# Sensor_Package.net
KiCad netlist of a schematic drawn in Altium Designer
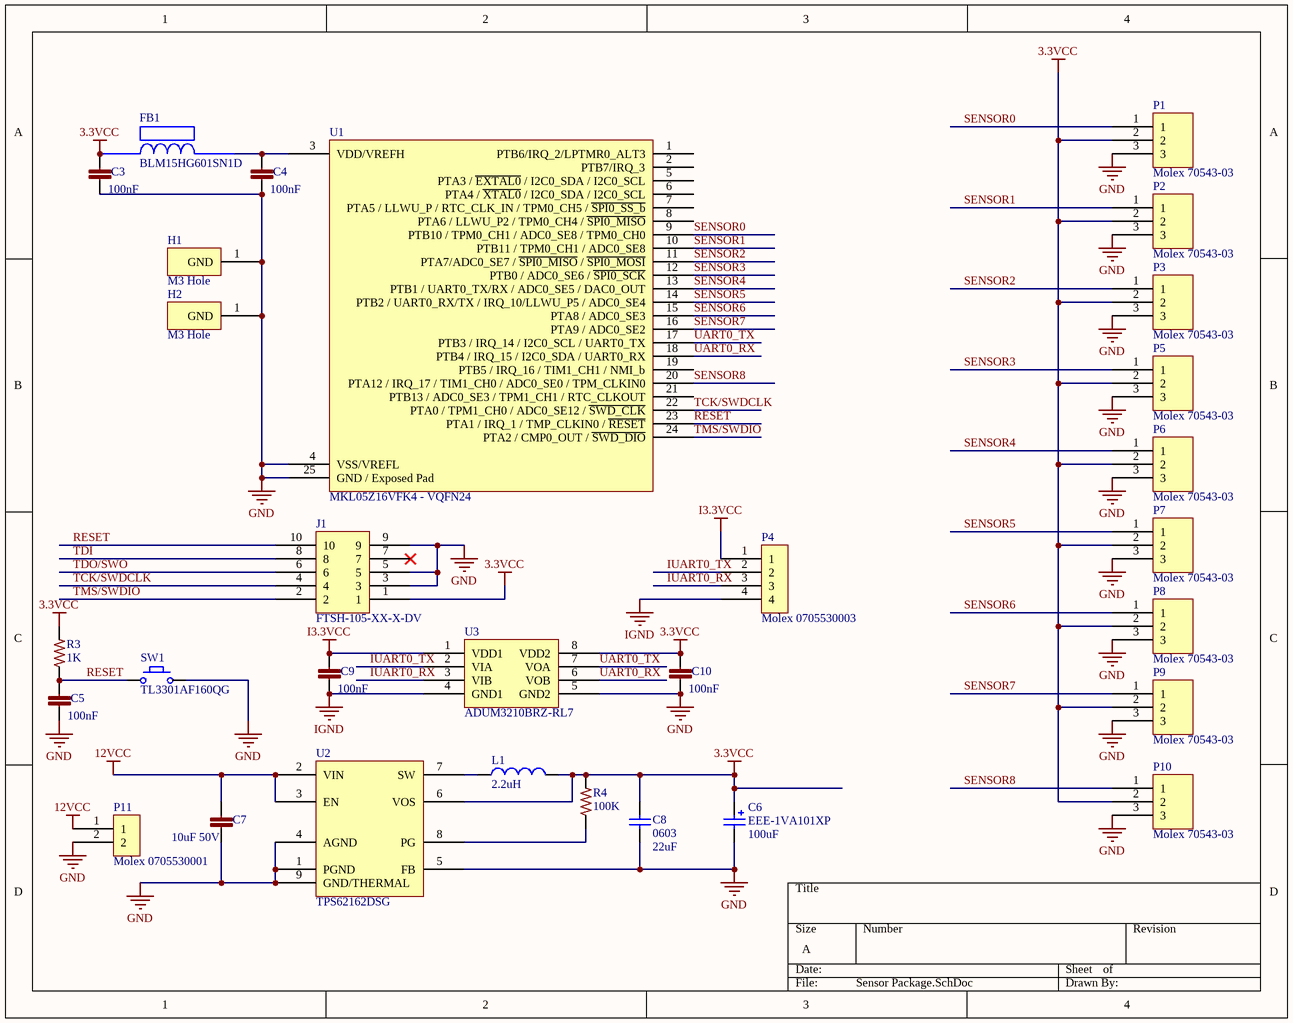
[diagram p0: Sensor Package.SchDoc]

(export (version "E")
  (design (tool "Eeschema 10.0.6"))
  (components
    (comp (ref "C3")
      (value "100nF")
      (footprint "C0402")
      (description "CAP CER 0402 100nF 16V 10% X7R")
      (fields
        (field (name "MANUFACTURERPARTNUMBER") "GRM155R71C104KA88D")
        (field (name "PUBLISHER") "UltiMachine")
      )
      (libsource (lib "3Delight") (part "GRM155R71C104KA88D"))
    )
    (comp (ref "C4")
      (value "100nF")
      (footprint "C0402")
      (description "CAP CER 0402 100nF 16V 10% X7R")
      (fields
        (field (name "MANUFACTURERPARTNUMBER") "GRM155R71C104KA88D")
        (field (name "PUBLISHER") "UltiMachine")
      )
      (libsource (lib "3Delight") (part "GRM155R71C104KA88D"))
    )
    (comp (ref "C5")
      (value "100nF")
      (footprint "C0402")
      (description "CAP CER 0402 100nF 16V 10% X7R")
      (fields
        (field (name "MANUFACTURERPARTNUMBER") "GRM155R71C104KA88D")
        (field (name "PUBLISHER") "UltiMachine")
      )
      (libsource (lib "3Delight") (part "GRM155R71C104KA88D"))
    )
    (comp (ref "C6")
      (value "EEE-1VA101XP")
      (footprint "EEE-1VA101XP")
      (description "CAP ALUM 100UF 35V 20% SMD")
      (fields (field (name "DIGIKEY PART #") "PCE3951CT-ND") (field (name "ALTIUM_VALUE") "100uF"))
      (libsource (lib "Tigershark3D") (part "EEE-1VA101XP"))
    )
    (comp (ref "C7")
      (value "10uF 50V")
      (footprint "C1206")
      (description "CAP CER 10UF 50V 10% X5R 1206")
      (fields
        (field (name "MANUFACTURER") "Samsung")
        (field (name "MANUFACTURERPARTNUMBER") "CL31A106KBHNNNE")
        (field (name "PUBLISHER") "UltiMachine")
      )
      (libsource (lib "Tigershark3D") (part "CL31A106KBHNNNE"))
    )
    (comp (ref "C8")
      (value "0603")
      (footprint "C0805")
      (description "CAP CER 22UF 6.3V 10% X5R 0805")
      (fields
        (field (name "MFR PART #") "CL21A226KQQNNNE")
        (field (name "MFR") "Samsung")
        (field (name "ALTIUM_VALUE") "22uF")
      )
      (libsource (lib "Sensor Package") (part "CL21A226KQQNNNE"))
    )
    (comp (ref "C9")
      (value "100nF")
      (footprint "C0402")
      (description "CAP CER 0402 100nF 16V 10% X7R")
      (fields
        (field (name "MANUFACTURERPARTNUMBER") "GRM155R71C104KA88D")
        (field (name "PUBLISHER") "UltiMachine")
      )
      (libsource (lib "3Delight") (part "GRM155R71C104KA88D"))
    )
    (comp (ref "C10")
      (value "100nF")
      (footprint "C0402")
      (description "CAP CER 0402 100nF 16V 10% X7R")
      (fields
        (field (name "MANUFACTURERPARTNUMBER") "GRM155R71C104KA88D")
        (field (name "PUBLISHER") "UltiMachine")
      )
      (libsource (lib "3Delight") (part "GRM155R71C104KA88D"))
    )
    (comp (ref "FB1")
      (value "BLM15HG601SN1D")
      (footprint "BLM18PG121SN1D")
      (libsource (lib "AHD Part Library") (part "BLM15HG601SN1D"))
    )
    (comp (ref "H1")
      (value "M3 Hole")
      (footprint "Hole-3mm")
      (description "3mm Hole")
      (libsource (lib "Sensor Package") (part "Hole"))
    )
    (comp (ref "H2")
      (value "M3 Hole")
      (footprint "Hole-3mm")
      (description "3mm Hole")
      (libsource (lib "Sensor Package") (part "Hole"))
    )
    (comp (ref "J1")
      (value "FTSH-105-XX-X-DV")
      (footprint "FTSH-105-XX-X-DV")
      (libsource (lib "Adams Altium Library") (part "ARM Cortex JTAG-DEBUG Header"))
    )
    (comp (ref "L1")
      (value "2.2uH")
      (footprint "VLS252012T-2R2M1R3")
      (description "VLS252012T-2R2M1R3")
      (fields (field (name "MFR") "TDK Corporation") (field (name "PUBLISHER") "Adam Vadala-Roth"))
      (libsource (lib "Sensor Package") (part "VLS252012T-2R2M1R3"))
    )
    (comp (ref "P1")
      (value "Molex 70543-03")
      (footprint "70543-03")
      (libsource (lib "RADMBo Schematic Library") (part "Molex Endstop"))
    )
    (comp (ref "P2")
      (value "Molex 70543-03")
      (footprint "70543-03")
      (libsource (lib "RADMBo Schematic Library") (part "Molex Endstop"))
    )
    (comp (ref "P3")
      (value "Molex 70543-03")
      (footprint "70543-03")
      (libsource (lib "RADMBo Schematic Library") (part "Molex Endstop"))
    )
    (comp (ref "P4")
      (value "Molex 0705530003")
      (footprint "0705530003")
      (description "Molex 0705530003 Right Angle 2.54mm Shrouded Header")
      (fields (field (name "MFR") "Molex"))
      (libsource (lib "Sensor Package") (part "0705530003"))
    )
    (comp (ref "P5")
      (value "Molex 70543-03")
      (footprint "70543-03")
      (libsource (lib "RADMBo Schematic Library") (part "Molex Endstop"))
    )
    (comp (ref "P6")
      (value "Molex 70543-03")
      (footprint "70543-03")
      (libsource (lib "RADMBo Schematic Library") (part "Molex Endstop"))
    )
    (comp (ref "P7")
      (value "Molex 70543-03")
      (footprint "70543-03")
      (libsource (lib "RADMBo Schematic Library") (part "Molex Endstop"))
    )
    (comp (ref "P8")
      (value "Molex 70543-03")
      (footprint "70543-03")
      (libsource (lib "RADMBo Schematic Library") (part "Molex Endstop"))
    )
    (comp (ref "P9")
      (value "Molex 70543-03")
      (footprint "70543-03")
      (libsource (lib "RADMBo Schematic Library") (part "Molex Endstop"))
    )
    (comp (ref "P10")
      (value "Molex 70543-03")
      (footprint "70543-03")
      (libsource (lib "RADMBo Schematic Library") (part "Molex Endstop"))
    )
    (comp (ref "P11")
      (value "Molex 0705530001")
      (footprint "0705530001")
      (description "Molex 0705530002 Right Angle 2.54mm Shrouded Header")
      (fields (field (name "MFR") "Molex"))
      (libsource (lib "Sensor Package") (part "0705530001"))
    )
    (comp (ref "R3")
      (value "1K")
      (footprint "R0603")
      (description "RES 0603 1K 100mW 1%")
      (fields
        (field (name "MANUFACTURERPARTNUMBER") "ERJ-3EKF1001V")
        (field (name "PUBLISHER") "UltiMachine")
      )
      (libsource (lib "3Delight") (part "ERJ-3EKF1001V"))
    )
    (comp (ref "R4")
      (value "100K")
      (footprint "R0603")
      (description "RES 100K OHM 1/10W 1% 0603 SMD")
      (fields
        (field (name "MANUFACTURERPARTNUMBER") "RC0603FR-07100KL")
        (field (name "PUBLISHER") "UltiMachine")
      )
      (libsource (lib "3Delight") (part "RC0603FR-07100KL"))
    )
    (comp (ref "SW1")
      (value "TL3301AF160QG")
      (footprint "TL3301AF160QG")
      (libsource (lib "MongoosMini") (part "TL3301AF160QG"))
    )
    (comp (ref "U1")
      (value "MKL05Z16VFK4 - VQFN24")
      (footprint "98ASA00474D")
      (description "ARM Cortex M0+")
      (libsource (lib "Encoder Fin") (part "MKL05Z16VFK4 - 24 Pin VQFN"))
    )
    (comp (ref "U2")
      (value "TPS62162DSG")
      (footprint "DSG8-1600X900TP")
      (libsource (lib "Adams Altium Library") (part "TPS62162SOP"))
    )
    (comp (ref "U3")
      (value "ADUM3210BRZ-RL7")
      (footprint "ADUM3210BRZ-RL7")
      (description "DGTL ISO 2.5KV GEN PURP 8SOIC")
      (fields (field (name "MFR") "Analog Devices"))
      (libsource (lib "Sensor Package") (part "ADUM3210BRZ-RL7"))
    )
  )
  (nets
    (net (code "1") (name "/IUART0_RX") (class "Default")
      (node (ref "P4") (pin "3") (pinfunction "3_3") (pintype "passive"))
      (node (ref "U3") (pin "3") (pinfunction "VIB_3") (pintype "passive"))
    )
    (net (code "2") (name "/IUART0_TX") (class "Default")
      (node (ref "P4") (pin "2") (pinfunction "2_2") (pintype "passive"))
      (node (ref "U3") (pin "2") (pinfunction "VIA_2") (pintype "passive"))
    )
    (net (code "3") (name "/RESET") (class "Default")
      (node (ref "C5") (pin "1") (pinfunction "1_1") (pintype "passive"))
      (node (ref "J1") (pin "10") (pinfunction "10_10") (pintype "passive"))
      (node (ref "R3") (pin "1") (pinfunction "1_1") (pintype "passive"))
      (node (ref "SW1") (pin "1") (pintype "passive"))
      (node (ref "U1") (pin "23") (pinfunction "PTA1_/_IRQ_1_/_TMP_CLKIN0_/_~{RESET}_23") (pintype "passive"))
    )
    (net (code "4") (name "/SENSOR0") (class "Default")
      (node (ref "P1") (pin "1") (pinfunction "1_1") (pintype "passive"))
      (node (ref "U1") (pin "9") (pinfunction "PTB10_/_TPM0_CH1_/_ADC0_SE8_/_TPM0_CH0_9") (pintype "passive"))
    )
    (net (code "5") (name "/SENSOR1") (class "Default")
      (node (ref "P2") (pin "1") (pinfunction "1_1") (pintype "passive"))
      (node (ref "U1") (pin "10") (pinfunction "PTB11_/_TPM0_CH1_/_ADC0_SE8_10") (pintype "passive"))
    )
    (net (code "6") (name "/SENSOR2") (class "Default")
      (node (ref "P3") (pin "1") (pinfunction "1_1") (pintype "passive"))
      (node (ref "U1") (pin "11") (pinfunction "PTA7/ADC0_SE7_/_~{SPI0_MISO}_/_~{SPI0_MOSI}_11") (pintype "passive"))
    )
    (net (code "7") (name "/SENSOR3") (class "Default")
      (node (ref "P5") (pin "1") (pinfunction "1_1") (pintype "passive"))
      (node (ref "U1") (pin "12") (pinfunction "PTB0_/_ADC0_SE6_/_~{SPI0_SCK}_12") (pintype "passive"))
    )
    (net (code "8") (name "/SENSOR4") (class "Default")
      (node (ref "P6") (pin "1") (pinfunction "1_1") (pintype "passive"))
      (node (ref "U1") (pin "13") (pinfunction "PTB1_/_UART0_TX/RX_/_ADC0_SE5_/_DAC0_OUT_13") (pintype "passive"))
    )
    (net (code "9") (name "/SENSOR5") (class "Default")
      (node (ref "P7") (pin "1") (pinfunction "1_1") (pintype "passive"))
      (node (ref "U1") (pin "14") (pinfunction "PTB2_/_UART0_RX/TX_/_IRQ_10/LLWU_P5_/_ADC0_SE4_14") (pintype "passive"))
    )
    (net (code "10") (name "/SENSOR6") (class "Default")
      (node (ref "P8") (pin "1") (pinfunction "1_1") (pintype "passive"))
      (node (ref "U1") (pin "15") (pinfunction "PTA8_/_ADC0_SE3_15") (pintype "passive"))
    )
    (net (code "11") (name "/SENSOR7") (class "Default")
      (node (ref "P9") (pin "1") (pinfunction "1_1") (pintype "passive"))
      (node (ref "U1") (pin "16") (pinfunction "PTA9_/_ADC0_SE2_16") (pintype "passive"))
    )
    (net (code "12") (name "/SENSOR8") (class "Default")
      (node (ref "P10") (pin "1") (pinfunction "1_1") (pintype "passive"))
      (node (ref "U1") (pin "20") (pinfunction "PTA12_/_IRQ_17_/_TIM1_CH0_/_ADC0_SE0_/_TPM_CLKIN0_20") (pintype "passive"))
    )
    (net (code "13") (name "/TCK{slash}SWDCLK") (class "Default")
      (node (ref "J1") (pin "4") (pinfunction "4_4") (pintype "passive"))
      (node (ref "U1") (pin "22") (pinfunction "PTA0_/_TPM1_CH0_/_ADC0_SE12_/_~{SWD_CLK}_22") (pintype "passive"))
    )
    (net (code "14") (name "/TDI") (class "Default")
      (node (ref "J1") (pin "8") (pinfunction "8_8") (pintype "passive"))
    )
    (net (code "15") (name "/TDO{slash}SWO") (class "Default")
      (node (ref "J1") (pin "6") (pinfunction "6_6") (pintype "passive"))
    )
    (net (code "16") (name "/TMS{slash}SWDIO") (class "Default")
      (node (ref "J1") (pin "2") (pinfunction "2_2") (pintype "passive"))
      (node (ref "U1") (pin "24") (pinfunction "PTA2_/_CMP0_OUT_/_~{SWD_DIO}_24") (pintype "passive"))
    )
    (net (code "17") (name "/UART0_RX") (class "Default")
      (node (ref "U1") (pin "18") (pinfunction "PTB4_/_IRQ_15_/_I2C0_SDA_/_UART0_RX_18") (pintype "passive"))
      (node (ref "U3") (pin "6") (pinfunction "VOB_6") (pintype "passive"))
    )
    (net (code "18") (name "/UART0_TX") (class "Default")
      (node (ref "U1") (pin "17") (pinfunction "PTB3_/_IRQ_14_/_I2C0_SCL_/_UART0_TX_17") (pintype "passive"))
      (node (ref "U3") (pin "7") (pinfunction "VOA_7") (pintype "passive"))
    )
    (net (code "19") (name "3.3VCC") (class "Default")
      (node (ref "C10") (pin "1") (pinfunction "1_1") (pintype "passive"))
      (node (ref "C3") (pin "1") (pinfunction "1_1") (pintype "passive"))
      (node (ref "C6") (pin "1") (pinfunction "1_1") (pintype "passive"))
      (node (ref "C8") (pin "2") (pinfunction "2_2") (pintype "passive"))
      (node (ref "FB1") (pin "1") (pinfunction "1_1") (pintype "passive"))
      (node (ref "J1") (pin "1") (pinfunction "1_1") (pintype "passive"))
      (node (ref "L1") (pin "2") (pinfunction "2_2") (pintype "passive"))
      (node (ref "P1") (pin "2") (pinfunction "2_2") (pintype "passive"))
      (node (ref "P10") (pin "2") (pinfunction "2_2") (pintype "passive"))
      (node (ref "P2") (pin "2") (pinfunction "2_2") (pintype "passive"))
      (node (ref "P3") (pin "2") (pinfunction "2_2") (pintype "passive"))
      (node (ref "P5") (pin "2") (pinfunction "2_2") (pintype "passive"))
      (node (ref "P6") (pin "2") (pinfunction "2_2") (pintype "passive"))
      (node (ref "P7") (pin "2") (pinfunction "2_2") (pintype "passive"))
      (node (ref "P8") (pin "2") (pinfunction "2_2") (pintype "passive"))
      (node (ref "P9") (pin "2") (pinfunction "2_2") (pintype "passive"))
      (node (ref "R3") (pin "2") (pinfunction "2_2") (pintype "passive"))
      (node (ref "R4") (pin "2") (pinfunction "2_2") (pintype "passive"))
      (node (ref "U2") (pin "6") (pinfunction "VOS_6") (pintype "passive"))
      (node (ref "U3") (pin "8") (pinfunction "VDD2_8") (pintype "passive"))
    )
    (net (code "20") (name "12VCC") (class "Default")
      (node (ref "C7") (pin "1") (pinfunction "1_1") (pintype "passive"))
      (node (ref "P11") (pin "1") (pinfunction "1_1") (pintype "passive"))
      (node (ref "U2") (pin "2") (pinfunction "VIN_2") (pintype "passive"))
      (node (ref "U2") (pin "3") (pinfunction "EN_3") (pintype "passive"))
    )
    (net (code "21") (name "GND") (class "Default")
      (node (ref "C10") (pin "2") (pinfunction "2_2") (pintype "passive"))
      (node (ref "C3") (pin "2") (pinfunction "2_2") (pintype "passive"))
      (node (ref "C4") (pin "2") (pinfunction "2_2") (pintype "passive"))
      (node (ref "C5") (pin "2") (pinfunction "2_2") (pintype "passive"))
      (node (ref "C6") (pin "2") (pinfunction "2_2") (pintype "passive"))
      (node (ref "C7") (pin "2") (pinfunction "2_2") (pintype "passive"))
      (node (ref "C8") (pin "1") (pinfunction "1_1") (pintype "passive"))
      (node (ref "H1") (pin "1") (pinfunction "GND_1") (pintype "passive"))
      (node (ref "H2") (pin "1") (pinfunction "GND_1") (pintype "passive"))
      (node (ref "J1") (pin "3") (pinfunction "3_3") (pintype "passive"))
      (node (ref "J1") (pin "5") (pinfunction "5_5") (pintype "passive"))
      (node (ref "J1") (pin "9") (pinfunction "9_9") (pintype "passive"))
      (node (ref "P1") (pin "3") (pinfunction "3_3") (pintype "passive"))
      (node (ref "P10") (pin "3") (pinfunction "3_3") (pintype "passive"))
      (node (ref "P11") (pin "2") (pinfunction "2_2") (pintype "passive"))
      (node (ref "P2") (pin "3") (pinfunction "3_3") (pintype "passive"))
      (node (ref "P3") (pin "3") (pinfunction "3_3") (pintype "passive"))
      (node (ref "P5") (pin "3") (pinfunction "3_3") (pintype "passive"))
      (node (ref "P6") (pin "3") (pinfunction "3_3") (pintype "passive"))
      (node (ref "P7") (pin "3") (pinfunction "3_3") (pintype "passive"))
      (node (ref "P8") (pin "3") (pinfunction "3_3") (pintype "passive"))
      (node (ref "P9") (pin "3") (pinfunction "3_3") (pintype "passive"))
      (node (ref "SW1") (pin "2") (pintype "passive"))
      (node (ref "U1") (pin "25") (pinfunction "GND_/_Exposed_Pad_25") (pintype "passive"))
      (node (ref "U1") (pin "4") (pinfunction "VSS/VREFL_4") (pintype "passive"))
      (node (ref "U2") (pin "1") (pinfunction "PGND_1") (pintype "passive"))
      (node (ref "U2") (pin "4") (pinfunction "AGND_4") (pintype "passive"))
      (node (ref "U2") (pin "5") (pinfunction "FB_5") (pintype "passive"))
      (node (ref "U2") (pin "9") (pinfunction "GND/THERMAL_9") (pintype "passive"))
      (node (ref "U3") (pin "5") (pinfunction "GND2_5") (pintype "passive"))
    )
    (net (code "22") (name "I3.3VCC") (class "Default")
      (node (ref "C9") (pin "1") (pinfunction "1_1") (pintype "passive"))
      (node (ref "P4") (pin "1") (pinfunction "1_1") (pintype "passive"))
      (node (ref "U3") (pin "1") (pinfunction "VDD1_1") (pintype "passive"))
    )
    (net (code "23") (name "IGND") (class "Default")
      (node (ref "C9") (pin "2") (pinfunction "2_2") (pintype "passive"))
      (node (ref "P4") (pin "4") (pinfunction "4_4") (pintype "passive"))
      (node (ref "U3") (pin "4") (pinfunction "GND1_4") (pintype "passive"))
    )
    (net (code "24") (name "Net-(U1-VDD{slash}VREFH)") (class "Default")
      (node (ref "C4") (pin "1") (pinfunction "1_1") (pintype "passive"))
      (node (ref "FB1") (pin "2") (pinfunction "2_2") (pintype "passive"))
      (node (ref "U1") (pin "3") (pinfunction "VDD/VREFH_3") (pintype "passive"))
    )
    (net (code "25") (name "Net-(U2-PG)") (class "Default")
      (node (ref "R4") (pin "1") (pinfunction "1_1") (pintype "passive"))
      (node (ref "U2") (pin "8") (pinfunction "PG_8") (pintype "passive"))
    )
    (net (code "26") (name "Net-(U2-SW)") (class "Default")
      (node (ref "L1") (pin "1") (pinfunction "1_1") (pintype "passive"))
      (node (ref "U2") (pin "7") (pinfunction "SW_7") (pintype "passive"))
    )
    (net (code "27") (name "unconnected-(J1-Pad7)") (class "Default")
      (node (ref "J1") (pin "7") (pinfunction "7_7") (pintype "passive+no_connect"))
    )
    (net (code "28") (name "unconnected-(U1-PTA3_{slash}_~{EXTAL0}_{slash}_I2C0_SDA_{slash}_I2C0_SCL-Pad5)") (class "Default")
      (node (ref "U1") (pin "5") (pinfunction "PTA3_/_~{EXTAL0}_/_I2C0_SDA_/_I2C0_SCL_5") (pintype "passive"))
    )
    (net (code "29") (name "unconnected-(U1-PTA4_{slash}_~{XTAL0}_{slash}_I2C0_SDA_{slash}_I2C0_SCL-Pad6)") (class "Default")
      (node (ref "U1") (pin "6") (pinfunction "PTA4_/_~{XTAL0}_/_I2C0_SDA_/_I2C0_SCL_6") (pintype "passive"))
    )
    (net (code "30") (name "unconnected-(U1-PTA5_{slash}_LLWU_P_{slash}_RTC_CLK_IN_{slash}_TPM0_CH5_{slash}_~{SPI0_SS_b}-Pad7)") (class "Default")
      (node (ref "U1") (pin "7") (pinfunction "PTA5_/_LLWU_P_/_RTC_CLK_IN_/_TPM0_CH5_/_~{SPI0_SS_b}_7") (pintype "passive"))
    )
    (net (code "31") (name "unconnected-(U1-PTA6_{slash}_LLWU_P2_{slash}_TPM0_CH4_{slash}_~{SPI0_MISO}-Pad8)") (class "Default")
      (node (ref "U1") (pin "8") (pinfunction "PTA6_/_LLWU_P2_/_TPM0_CH4_/_~{SPI0_MISO}_8") (pintype "passive"))
    )
    (net (code "32") (name "unconnected-(U1-PTB5_{slash}_IRQ_16_{slash}_TIM1_CH1_{slash}_NMI_b-Pad19)") (class "Default")
      (node (ref "U1") (pin "19") (pinfunction "PTB5_/_IRQ_16_/_TIM1_CH1_/_NMI_b_19") (pintype "passive"))
    )
    (net (code "33") (name "unconnected-(U1-PTB6{slash}IRQ_2{slash}LPTMR0_ALT3-Pad1)") (class "Default")
      (node (ref "U1") (pin "1") (pinfunction "PTB6/IRQ_2/LPTMR0_ALT3_1") (pintype "passive"))
    )
    (net (code "34") (name "unconnected-(U1-PTB7{slash}IRQ_3-Pad2)") (class "Default")
      (node (ref "U1") (pin "2") (pinfunction "PTB7/IRQ_3_2") (pintype "passive"))
    )
    (net (code "35") (name "unconnected-(U1-PTB13_{slash}_ADC0_SE3_{slash}_TPM1_CH1_{slash}_RTC_CLKOUT-Pad21)") (class "Default")
      (node (ref "U1") (pin "21") (pinfunction "PTB13_/_ADC0_SE3_/_TPM1_CH1_/_RTC_CLKOUT_21") (pintype "passive"))
    )
  )
)
